# SCH_CourseWorkMk_2022-09-30_2.net
KiCad netlist of a schematic drawn in EasyEDA
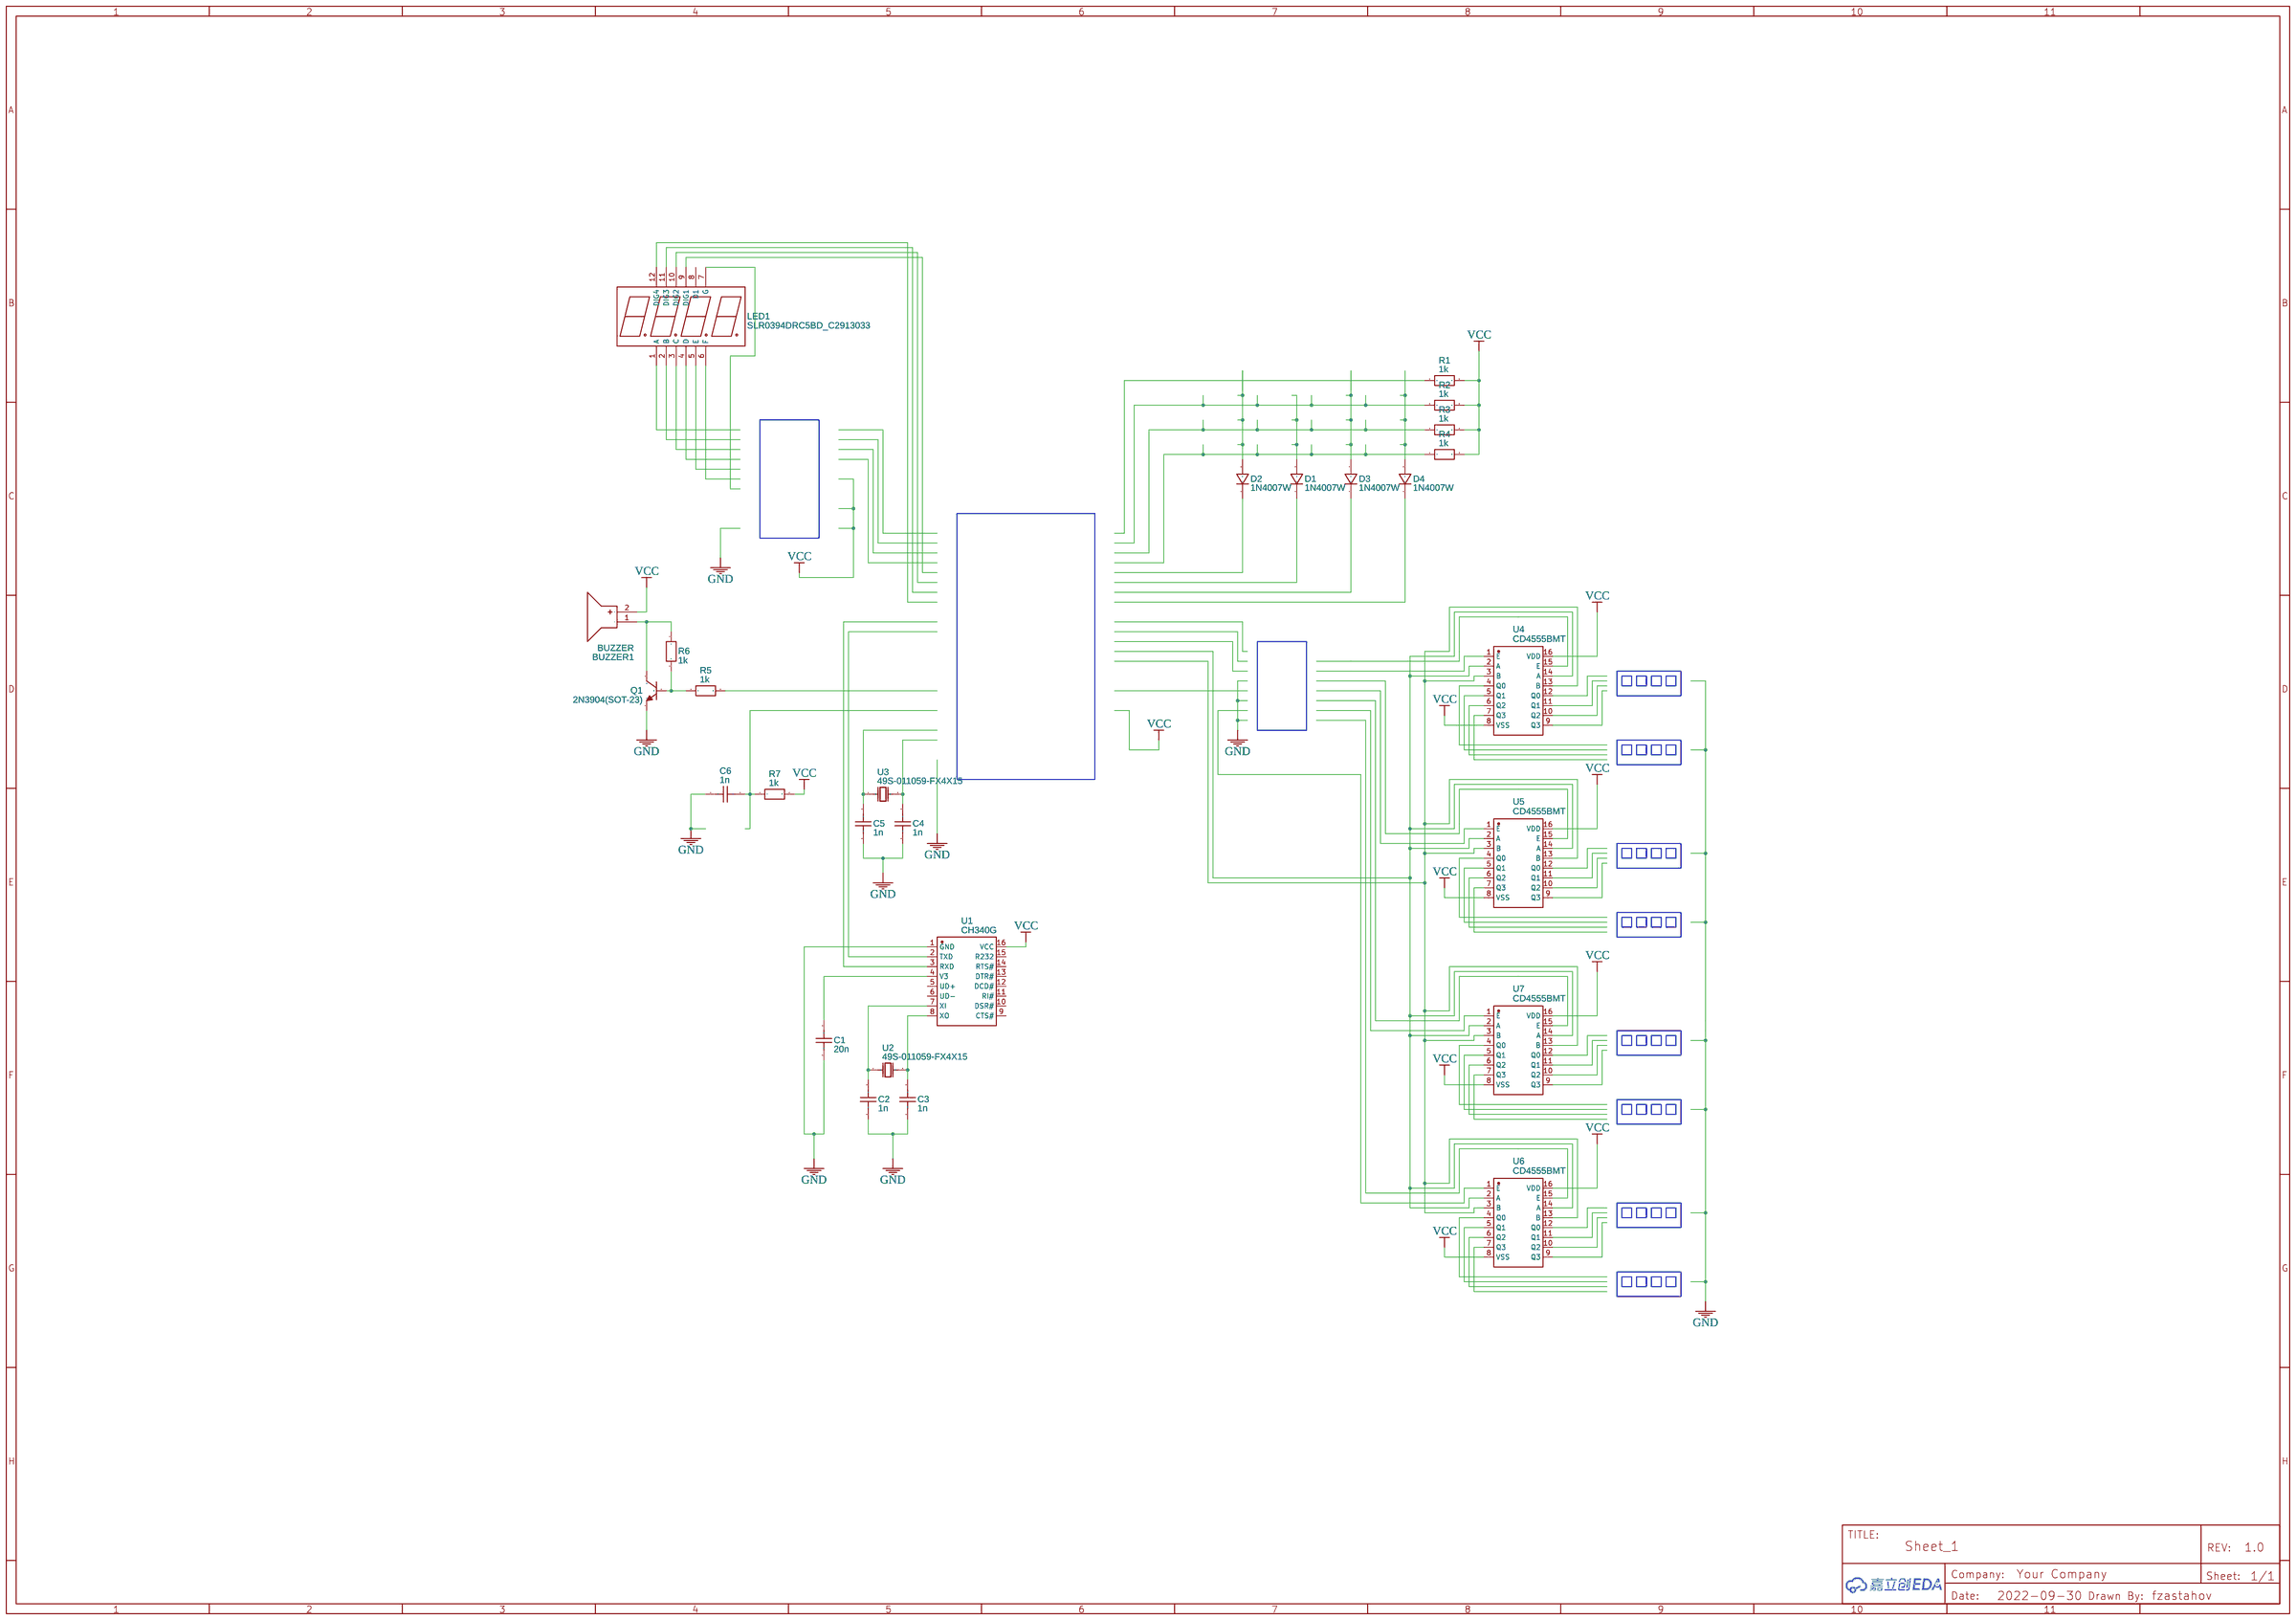
[diagram p0: schematic sheet]

(export (version "E")
  (design (tool "Eeschema 10.0.6"))
  (components
    (comp (ref "BUZZER1")
      (value "BUZZER")
      (fields
        (field (name "BOM_Manufacturer Part") "buzzer")
        (field (name "BOM_Supplier Part") "C9900014030")
      )
      (libsource (lib "") (part "BUZZER"))
    )
    (comp (ref "C1") (value "20n") (libsource (lib "") (part "C_0603_US")))
    (comp (ref "C2") (value "1n") (libsource (lib "") (part "C_0603_US")))
    (comp (ref "C3") (value "1n") (libsource (lib "") (part "C_0603_US")))
    (comp (ref "C4") (value "1n") (libsource (lib "") (part "C_0603_US")))
    (comp (ref "C5") (value "1n") (libsource (lib "") (part "C_0603_US")))
    (comp (ref "C6") (value "1n") (libsource (lib "") (part "C_0603_US_1")))
    (comp (ref "D1")
      (value "1N4007W")
      (fields (field (name "BOM_Supplier Part") "C328592"))
      (libsource (lib "") (part "1N4007W"))
    )
    (comp (ref "D2")
      (value "1N4007W")
      (fields (field (name "BOM_Supplier Part") "C328592"))
      (libsource (lib "") (part "1N4007W"))
    )
    (comp (ref "D3")
      (value "1N4007W")
      (fields (field (name "BOM_Supplier Part") "C328592"))
      (libsource (lib "") (part "1N4007W"))
    )
    (comp (ref "D4")
      (value "1N4007W")
      (fields (field (name "BOM_Supplier Part") "C328592"))
      (libsource (lib "") (part "1N4007W"))
    )
    (comp (ref "LED1")
      (value "SLR0394DRC5BD_C2913033")
      (fields
        (field (name "BOM_Manufacturer Part") "SLR0394DRC5BD")
        (field (name "BOM_Supplier Part") "C2913033")
      )
      (libsource (lib "") (part "SLR0394DRC5BD_C2913033"))
    )
    (comp (ref "Q1")
      (value "2N3904(SOT-23)")
      (fields
        (field (name "BOM_Manufacturer Part") "2n3904S-RTK/PS")
        (field (name "BOM_Supplier Part") "C18536")
      )
      (libsource (lib "") (part "2N3904(SOT-23)"))
    )
    (comp (ref "R1") (value "1k") (libsource (lib "") (part "R_0603_EU")))
    (comp (ref "R2") (value "1k") (libsource (lib "") (part "R_0603_EU")))
    (comp (ref "R3") (value "1k") (libsource (lib "") (part "R_0603_EU")))
    (comp (ref "R4") (value "1k") (libsource (lib "") (part "R_0603_EU")))
    (comp (ref "R5") (value "1k") (libsource (lib "") (part "R_0603_EU")))
    (comp (ref "R6") (value "1k") (libsource (lib "") (part "R_0603_EU_1")))
    (comp (ref "R7") (value "1k") (libsource (lib "") (part "R_0603_EU")))
    (comp (ref "U1")
      (value "CH340G")
      (fields (field (name "BOM_Supplier Part") "C14267"))
      (libsource (lib "") (part "CH340G"))
    )
    (comp (ref "U2")
      (value "49S-011059-FX4X15")
      (fields (field (name "BOM_Supplier Part") "C470253"))
      (libsource (lib "") (part "49S-011059-FX4X15"))
    )
    (comp (ref "U3")
      (value "49S-011059-FX4X15")
      (fields (field (name "BOM_Supplier Part") "C470253"))
      (libsource (lib "") (part "49S-011059-FX4X15"))
    )
    (comp (ref "U4")
      (value "CD4555BMT")
      (fields (field (name "BOM_Supplier Part") "C1879855"))
      (libsource (lib "") (part "CD4555BMT"))
    )
    (comp (ref "U5")
      (value "CD4555BMT")
      (fields (field (name "BOM_Supplier Part") "C1879855"))
      (libsource (lib "") (part "CD4555BMT"))
    )
    (comp (ref "U6")
      (value "CD4555BMT")
      (fields (field (name "BOM_Supplier Part") "C1879855"))
      (libsource (lib "") (part "CD4555BMT"))
    )
    (comp (ref "U7")
      (value "CD4555BMT")
      (fields (field (name "BOM_Supplier Part") "C1879855"))
      (libsource (lib "") (part "CD4555BMT"))
    )
  )
  (nets
    (net (code "1") (name "GND") (class "Default")
      (node (ref "C1") (pin "2") (pinfunction "2_2") (pintype "unspecified"))
      (node (ref "C2") (pin "2") (pinfunction "2_2") (pintype "unspecified"))
      (node (ref "C3") (pin "2") (pinfunction "2_2") (pintype "unspecified"))
      (node (ref "C4") (pin "2") (pinfunction "2_2") (pintype "unspecified"))
      (node (ref "C5") (pin "2") (pinfunction "2_2") (pintype "unspecified"))
      (node (ref "C6") (pin "1") (pinfunction "1_1") (pintype "unspecified"))
      (node (ref "Q1") (pin "1") (pinfunction "E_1") (pintype "input"))
      (node (ref "U1") (pin "1") (pinfunction "GND_1") (pintype "unspecified"))
    )
    (net (code "2") (name "Net-(BUZZER1--)") (class "Default")
      (node (ref "BUZZER1") (pin "1") (pinfunction "-_1") (pintype "unspecified"))
      (node (ref "Q1") (pin "3") (pinfunction "C_3") (pintype "input"))
      (node (ref "R6") (pin "1") (pinfunction "1_1") (pintype "unspecified"))
    )
    (net (code "3") (name "Net-(C6-Pad2)") (class "Default")
      (node (ref "C6") (pin "2") (pinfunction "2_2") (pintype "unspecified"))
      (node (ref "R7") (pin "1") (pinfunction "1_1") (pintype "unspecified"))
    )
    (net (code "4") (name "Net-(Q1-B)") (class "Default")
      (node (ref "Q1") (pin "2") (pinfunction "B_2") (pintype "input"))
      (node (ref "R5") (pin "1") (pinfunction "1_1") (pintype "unspecified"))
      (node (ref "R6") (pin "2") (pinfunction "2_2") (pintype "unspecified"))
    )
    (net (code "5") (name "Net-(U1-V3)") (class "Default")
      (node (ref "C1") (pin "1") (pinfunction "1_1") (pintype "unspecified"))
      (node (ref "U1") (pin "4") (pinfunction "V3_4") (pintype "unspecified"))
    )
    (net (code "6") (name "Net-(U1-XI)") (class "Default")
      (node (ref "C2") (pin "1") (pinfunction "1_1") (pintype "unspecified"))
      (node (ref "U1") (pin "7") (pinfunction "XI_7") (pintype "unspecified"))
      (node (ref "U2") (pin "1") (pinfunction "OSC1_1") (pintype "input"))
    )
    (net (code "7") (name "Net-(U1-XO)") (class "Default")
      (node (ref "C3") (pin "1") (pinfunction "1_1") (pintype "unspecified"))
      (node (ref "U1") (pin "8") (pinfunction "XO_8") (pintype "unspecified"))
      (node (ref "U2") (pin "2") (pinfunction "OSC2_2") (pintype "input"))
    )
    (net (code "8") (name "Net-(U3-OSC1)") (class "Default")
      (node (ref "C5") (pin "1") (pinfunction "1_1") (pintype "unspecified"))
      (node (ref "U3") (pin "1") (pinfunction "OSC1_1") (pintype "input"))
    )
    (net (code "9") (name "Net-(U3-OSC2)") (class "Default")
      (node (ref "C4") (pin "1") (pinfunction "1_1") (pintype "unspecified"))
      (node (ref "U3") (pin "2") (pinfunction "OSC2_2") (pintype "input"))
    )
    (net (code "10") (name "Net-(U4-A-Pad14)") (class "Default")
      (node (ref "U4") (pin "14") (pinfunction "A_14") (pintype "unspecified"))
      (node (ref "U4") (pin "2") (pinfunction "A_2") (pintype "unspecified"))
      (node (ref "U5") (pin "14") (pinfunction "A_14") (pintype "unspecified"))
      (node (ref "U5") (pin "2") (pinfunction "A_2") (pintype "unspecified"))
      (node (ref "U6") (pin "14") (pinfunction "A_14") (pintype "unspecified"))
      (node (ref "U6") (pin "2") (pinfunction "A_2") (pintype "unspecified"))
      (node (ref "U7") (pin "14") (pinfunction "A_14") (pintype "unspecified"))
      (node (ref "U7") (pin "2") (pinfunction "A_2") (pintype "unspecified"))
    )
    (net (code "11") (name "Net-(U4-B-Pad13)") (class "Default")
      (node (ref "U4") (pin "13") (pinfunction "B_13") (pintype "unspecified"))
      (node (ref "U4") (pin "3") (pinfunction "B_3") (pintype "unspecified"))
      (node (ref "U5") (pin "13") (pinfunction "B_13") (pintype "unspecified"))
      (node (ref "U5") (pin "3") (pinfunction "B_3") (pintype "unspecified"))
      (node (ref "U6") (pin "13") (pinfunction "B_13") (pintype "unspecified"))
      (node (ref "U6") (pin "3") (pinfunction "B_3") (pintype "unspecified"))
      (node (ref "U7") (pin "13") (pinfunction "B_13") (pintype "unspecified"))
      (node (ref "U7") (pin "3") (pinfunction "B_3") (pintype "unspecified"))
    )
    (net (code "12") (name "VCC") (class "Default")
      (node (ref "BUZZER1") (pin "2") (pinfunction "+_2") (pintype "unspecified"))
      (node (ref "R1") (pin "2") (pinfunction "2_2") (pintype "unspecified"))
      (node (ref "R2") (pin "2") (pinfunction "2_2") (pintype "unspecified"))
      (node (ref "R3") (pin "2") (pinfunction "2_2") (pintype "unspecified"))
      (node (ref "R4") (pin "2") (pinfunction "2_2") (pintype "unspecified"))
      (node (ref "R7") (pin "2") (pinfunction "2_2") (pintype "unspecified"))
      (node (ref "U1") (pin "16") (pinfunction "VCC_16") (pintype "unspecified"))
      (node (ref "U4") (pin "16") (pinfunction "VDD_16") (pintype "unspecified"))
      (node (ref "U4") (pin "8") (pinfunction "VSS_8") (pintype "unspecified"))
      (node (ref "U5") (pin "16") (pinfunction "VDD_16") (pintype "unspecified"))
      (node (ref "U5") (pin "8") (pinfunction "VSS_8") (pintype "unspecified"))
      (node (ref "U6") (pin "16") (pinfunction "VDD_16") (pintype "unspecified"))
      (node (ref "U6") (pin "8") (pinfunction "VSS_8") (pintype "unspecified"))
      (node (ref "U7") (pin "16") (pinfunction "VDD_16") (pintype "unspecified"))
      (node (ref "U7") (pin "8") (pinfunction "VSS_8") (pintype "unspecified"))
    )
    (net (code "13") (name "unconnected-(D1-Pad1)") (class "Default")
      (node (ref "D1") (pin "1") (pinfunction "1_1") (pintype "unspecified"))
    )
    (net (code "14") (name "unconnected-(D1-Pad2)") (class "Default")
      (node (ref "D1") (pin "2") (pinfunction "2_2") (pintype "unspecified"))
    )
    (net (code "15") (name "unconnected-(D2-Pad1)") (class "Default")
      (node (ref "D2") (pin "1") (pinfunction "1_1") (pintype "unspecified"))
    )
    (net (code "16") (name "unconnected-(D2-Pad2)") (class "Default")
      (node (ref "D2") (pin "2") (pinfunction "2_2") (pintype "unspecified"))
    )
    (net (code "17") (name "unconnected-(D3-Pad1)") (class "Default")
      (node (ref "D3") (pin "1") (pinfunction "1_1") (pintype "unspecified"))
    )
    (net (code "18") (name "unconnected-(D3-Pad2)") (class "Default")
      (node (ref "D3") (pin "2") (pinfunction "2_2") (pintype "unspecified"))
    )
    (net (code "19") (name "unconnected-(D4-Pad1)") (class "Default")
      (node (ref "D4") (pin "1") (pinfunction "1_1") (pintype "unspecified"))
    )
    (net (code "20") (name "unconnected-(D4-Pad2)") (class "Default")
      (node (ref "D4") (pin "2") (pinfunction "2_2") (pintype "unspecified"))
    )
    (net (code "21") (name "unconnected-(LED1-A-Pad1)") (class "Default")
      (node (ref "LED1") (pin "1") (pinfunction "A_1") (pintype "unspecified"))
    )
    (net (code "22") (name "unconnected-(LED1-B-Pad2)") (class "Default")
      (node (ref "LED1") (pin "2") (pinfunction "B_2") (pintype "unspecified"))
    )
    (net (code "23") (name "unconnected-(LED1-C-Pad3)") (class "Default")
      (node (ref "LED1") (pin "3") (pinfunction "C_3") (pintype "unspecified"))
    )
    (net (code "24") (name "unconnected-(LED1-D-Pad4)") (class "Default")
      (node (ref "LED1") (pin "4") (pinfunction "D_4") (pintype "unspecified"))
    )
    (net (code "25") (name "unconnected-(LED1-D1-Pad8)") (class "Default")
      (node (ref "LED1") (pin "8") (pinfunction "D1_8") (pintype "unspecified"))
    )
    (net (code "26") (name "unconnected-(LED1-DIG1-Pad9)") (class "Default")
      (node (ref "LED1") (pin "9") (pinfunction "DIG1_9") (pintype "unspecified"))
    )
    (net (code "27") (name "unconnected-(LED1-DIG2-Pad10)") (class "Default")
      (node (ref "LED1") (pin "10") (pinfunction "DIG2_10") (pintype "unspecified"))
    )
    (net (code "28") (name "unconnected-(LED1-DIG3-Pad11)") (class "Default")
      (node (ref "LED1") (pin "11") (pinfunction "DIG3_11") (pintype "unspecified"))
    )
    (net (code "29") (name "unconnected-(LED1-DIG4-Pad12)") (class "Default")
      (node (ref "LED1") (pin "12") (pinfunction "DIG4_12") (pintype "unspecified"))
    )
    (net (code "30") (name "unconnected-(LED1-E-Pad5)") (class "Default")
      (node (ref "LED1") (pin "5") (pinfunction "E_5") (pintype "unspecified"))
    )
    (net (code "31") (name "unconnected-(LED1-F-Pad6)") (class "Default")
      (node (ref "LED1") (pin "6") (pinfunction "F_6") (pintype "unspecified"))
    )
    (net (code "32") (name "unconnected-(LED1-G-Pad7)") (class "Default")
      (node (ref "LED1") (pin "7") (pinfunction "G_7") (pintype "unspecified"))
    )
    (net (code "33") (name "unconnected-(R1-Pad1)") (class "Default")
      (node (ref "R1") (pin "1") (pinfunction "1_1") (pintype "unspecified"))
    )
    (net (code "34") (name "unconnected-(R2-Pad1)") (class "Default")
      (node (ref "R2") (pin "1") (pinfunction "1_1") (pintype "unspecified"))
    )
    (net (code "35") (name "unconnected-(R3-Pad1)") (class "Default")
      (node (ref "R3") (pin "1") (pinfunction "1_1") (pintype "unspecified"))
    )
    (net (code "36") (name "unconnected-(R4-Pad1)") (class "Default")
      (node (ref "R4") (pin "1") (pinfunction "1_1") (pintype "unspecified"))
    )
    (net (code "37") (name "unconnected-(R5-Pad2)") (class "Default")
      (node (ref "R5") (pin "2") (pinfunction "2_2") (pintype "unspecified"))
    )
    (net (code "38") (name "unconnected-(U1-CTS#-Pad9)") (class "Default")
      (node (ref "U1") (pin "9") (pinfunction "CTS#_9") (pintype "unspecified"))
    )
    (net (code "39") (name "unconnected-(U1-DCD#-Pad12)") (class "Default")
      (node (ref "U1") (pin "12") (pinfunction "DCD#_12") (pintype "unspecified"))
    )
    (net (code "40") (name "unconnected-(U1-DSR#-Pad10)") (class "Default")
      (node (ref "U1") (pin "10") (pinfunction "DSR#_10") (pintype "unspecified"))
    )
    (net (code "41") (name "unconnected-(U1-DTR#-Pad13)") (class "Default")
      (node (ref "U1") (pin "13") (pinfunction "DTR#_13") (pintype "unspecified"))
    )
    (net (code "42") (name "unconnected-(U1-R232-Pad15)") (class "Default")
      (node (ref "U1") (pin "15") (pinfunction "R232_15") (pintype "unspecified"))
    )
    (net (code "43") (name "unconnected-(U1-RI#-Pad11)") (class "Default")
      (node (ref "U1") (pin "11") (pinfunction "RI#_11") (pintype "unspecified"))
    )
    (net (code "44") (name "unconnected-(U1-RTS#-Pad14)") (class "Default")
      (node (ref "U1") (pin "14") (pinfunction "RTS#_14") (pintype "unspecified"))
    )
    (net (code "45") (name "unconnected-(U1-RXD-Pad3)") (class "Default")
      (node (ref "U1") (pin "3") (pinfunction "RXD_3") (pintype "unspecified"))
    )
    (net (code "46") (name "unconnected-(U1-TXD-Pad2)") (class "Default")
      (node (ref "U1") (pin "2") (pinfunction "TXD_2") (pintype "unspecified"))
    )
    (net (code "47") (name "unconnected-(U1-UD+-Pad5)") (class "Default")
      (node (ref "U1") (pin "5") (pinfunction "UD+_5") (pintype "unspecified"))
    )
    (net (code "48") (name "unconnected-(U1-UD--Pad6)") (class "Default")
      (node (ref "U1") (pin "6") (pinfunction "UD-_6") (pintype "unspecified"))
    )
    (net (code "49") (name "unconnected-(U4-E-Pad1)") (class "Default")
      (node (ref "U4") (pin "1") (pinfunction "E_1") (pintype "unspecified"))
    )
    (net (code "50") (name "unconnected-(U4-E-Pad15)") (class "Default")
      (node (ref "U4") (pin "15") (pinfunction "E_15") (pintype "unspecified"))
    )
    (net (code "51") (name "unconnected-(U4-Q0-Pad4)") (class "Default")
      (node (ref "U4") (pin "4") (pinfunction "Q0_4") (pintype "unspecified"))
    )
    (net (code "52") (name "unconnected-(U4-Q0-Pad12)") (class "Default")
      (node (ref "U4") (pin "12") (pinfunction "Q0_12") (pintype "unspecified"))
    )
    (net (code "53") (name "unconnected-(U4-Q1-Pad5)") (class "Default")
      (node (ref "U4") (pin "5") (pinfunction "Q1_5") (pintype "unspecified"))
    )
    (net (code "54") (name "unconnected-(U4-Q1-Pad11)") (class "Default")
      (node (ref "U4") (pin "11") (pinfunction "Q1_11") (pintype "unspecified"))
    )
    (net (code "55") (name "unconnected-(U4-Q2-Pad6)") (class "Default")
      (node (ref "U4") (pin "6") (pinfunction "Q2_6") (pintype "unspecified"))
    )
    (net (code "56") (name "unconnected-(U4-Q2-Pad10)") (class "Default")
      (node (ref "U4") (pin "10") (pinfunction "Q2_10") (pintype "unspecified"))
    )
    (net (code "57") (name "unconnected-(U4-Q3-Pad7)") (class "Default")
      (node (ref "U4") (pin "7") (pinfunction "Q3_7") (pintype "unspecified"))
    )
    (net (code "58") (name "unconnected-(U4-Q3-Pad9)") (class "Default")
      (node (ref "U4") (pin "9") (pinfunction "Q3_9") (pintype "unspecified"))
    )
    (net (code "59") (name "unconnected-(U5-E-Pad1)") (class "Default")
      (node (ref "U5") (pin "1") (pinfunction "E_1") (pintype "unspecified"))
    )
    (net (code "60") (name "unconnected-(U5-E-Pad15)") (class "Default")
      (node (ref "U5") (pin "15") (pinfunction "E_15") (pintype "unspecified"))
    )
    (net (code "61") (name "unconnected-(U5-Q0-Pad4)") (class "Default")
      (node (ref "U5") (pin "4") (pinfunction "Q0_4") (pintype "unspecified"))
    )
    (net (code "62") (name "unconnected-(U5-Q0-Pad12)") (class "Default")
      (node (ref "U5") (pin "12") (pinfunction "Q0_12") (pintype "unspecified"))
    )
    (net (code "63") (name "unconnected-(U5-Q1-Pad5)") (class "Default")
      (node (ref "U5") (pin "5") (pinfunction "Q1_5") (pintype "unspecified"))
    )
    (net (code "64") (name "unconnected-(U5-Q1-Pad11)") (class "Default")
      (node (ref "U5") (pin "11") (pinfunction "Q1_11") (pintype "unspecified"))
    )
    (net (code "65") (name "unconnected-(U5-Q2-Pad6)") (class "Default")
      (node (ref "U5") (pin "6") (pinfunction "Q2_6") (pintype "unspecified"))
    )
    (net (code "66") (name "unconnected-(U5-Q2-Pad10)") (class "Default")
      (node (ref "U5") (pin "10") (pinfunction "Q2_10") (pintype "unspecified"))
    )
    (net (code "67") (name "unconnected-(U5-Q3-Pad7)") (class "Default")
      (node (ref "U5") (pin "7") (pinfunction "Q3_7") (pintype "unspecified"))
    )
    (net (code "68") (name "unconnected-(U5-Q3-Pad9)") (class "Default")
      (node (ref "U5") (pin "9") (pinfunction "Q3_9") (pintype "unspecified"))
    )
    (net (code "69") (name "unconnected-(U6-E-Pad1)") (class "Default")
      (node (ref "U6") (pin "1") (pinfunction "E_1") (pintype "unspecified"))
    )
    (net (code "70") (name "unconnected-(U6-E-Pad15)") (class "Default")
      (node (ref "U6") (pin "15") (pinfunction "E_15") (pintype "unspecified"))
    )
    (net (code "71") (name "unconnected-(U6-Q0-Pad4)") (class "Default")
      (node (ref "U6") (pin "4") (pinfunction "Q0_4") (pintype "unspecified"))
    )
    (net (code "72") (name "unconnected-(U6-Q0-Pad12)") (class "Default")
      (node (ref "U6") (pin "12") (pinfunction "Q0_12") (pintype "unspecified"))
    )
    (net (code "73") (name "unconnected-(U6-Q1-Pad5)") (class "Default")
      (node (ref "U6") (pin "5") (pinfunction "Q1_5") (pintype "unspecified"))
    )
    (net (code "74") (name "unconnected-(U6-Q1-Pad11)") (class "Default")
      (node (ref "U6") (pin "11") (pinfunction "Q1_11") (pintype "unspecified"))
    )
    (net (code "75") (name "unconnected-(U6-Q2-Pad6)") (class "Default")
      (node (ref "U6") (pin "6") (pinfunction "Q2_6") (pintype "unspecified"))
    )
    (net (code "76") (name "unconnected-(U6-Q2-Pad10)") (class "Default")
      (node (ref "U6") (pin "10") (pinfunction "Q2_10") (pintype "unspecified"))
    )
    (net (code "77") (name "unconnected-(U6-Q3-Pad7)") (class "Default")
      (node (ref "U6") (pin "7") (pinfunction "Q3_7") (pintype "unspecified"))
    )
    (net (code "78") (name "unconnected-(U6-Q3-Pad9)") (class "Default")
      (node (ref "U6") (pin "9") (pinfunction "Q3_9") (pintype "unspecified"))
    )
    (net (code "79") (name "unconnected-(U7-E-Pad1)") (class "Default")
      (node (ref "U7") (pin "1") (pinfunction "E_1") (pintype "unspecified"))
    )
    (net (code "80") (name "unconnected-(U7-E-Pad15)") (class "Default")
      (node (ref "U7") (pin "15") (pinfunction "E_15") (pintype "unspecified"))
    )
    (net (code "81") (name "unconnected-(U7-Q0-Pad4)") (class "Default")
      (node (ref "U7") (pin "4") (pinfunction "Q0_4") (pintype "unspecified"))
    )
    (net (code "82") (name "unconnected-(U7-Q0-Pad12)") (class "Default")
      (node (ref "U7") (pin "12") (pinfunction "Q0_12") (pintype "unspecified"))
    )
    (net (code "83") (name "unconnected-(U7-Q1-Pad5)") (class "Default")
      (node (ref "U7") (pin "5") (pinfunction "Q1_5") (pintype "unspecified"))
    )
    (net (code "84") (name "unconnected-(U7-Q1-Pad11)") (class "Default")
      (node (ref "U7") (pin "11") (pinfunction "Q1_11") (pintype "unspecified"))
    )
    (net (code "85") (name "unconnected-(U7-Q2-Pad6)") (class "Default")
      (node (ref "U7") (pin "6") (pinfunction "Q2_6") (pintype "unspecified"))
    )
    (net (code "86") (name "unconnected-(U7-Q2-Pad10)") (class "Default")
      (node (ref "U7") (pin "10") (pinfunction "Q2_10") (pintype "unspecified"))
    )
    (net (code "87") (name "unconnected-(U7-Q3-Pad7)") (class "Default")
      (node (ref "U7") (pin "7") (pinfunction "Q3_7") (pintype "unspecified"))
    )
    (net (code "88") (name "unconnected-(U7-Q3-Pad9)") (class "Default")
      (node (ref "U7") (pin "9") (pinfunction "Q3_9") (pintype "unspecified"))
    )
  )
)
